# 03_-MPU6050.net
KiCad netlist of a schematic drawn in Altium Designer
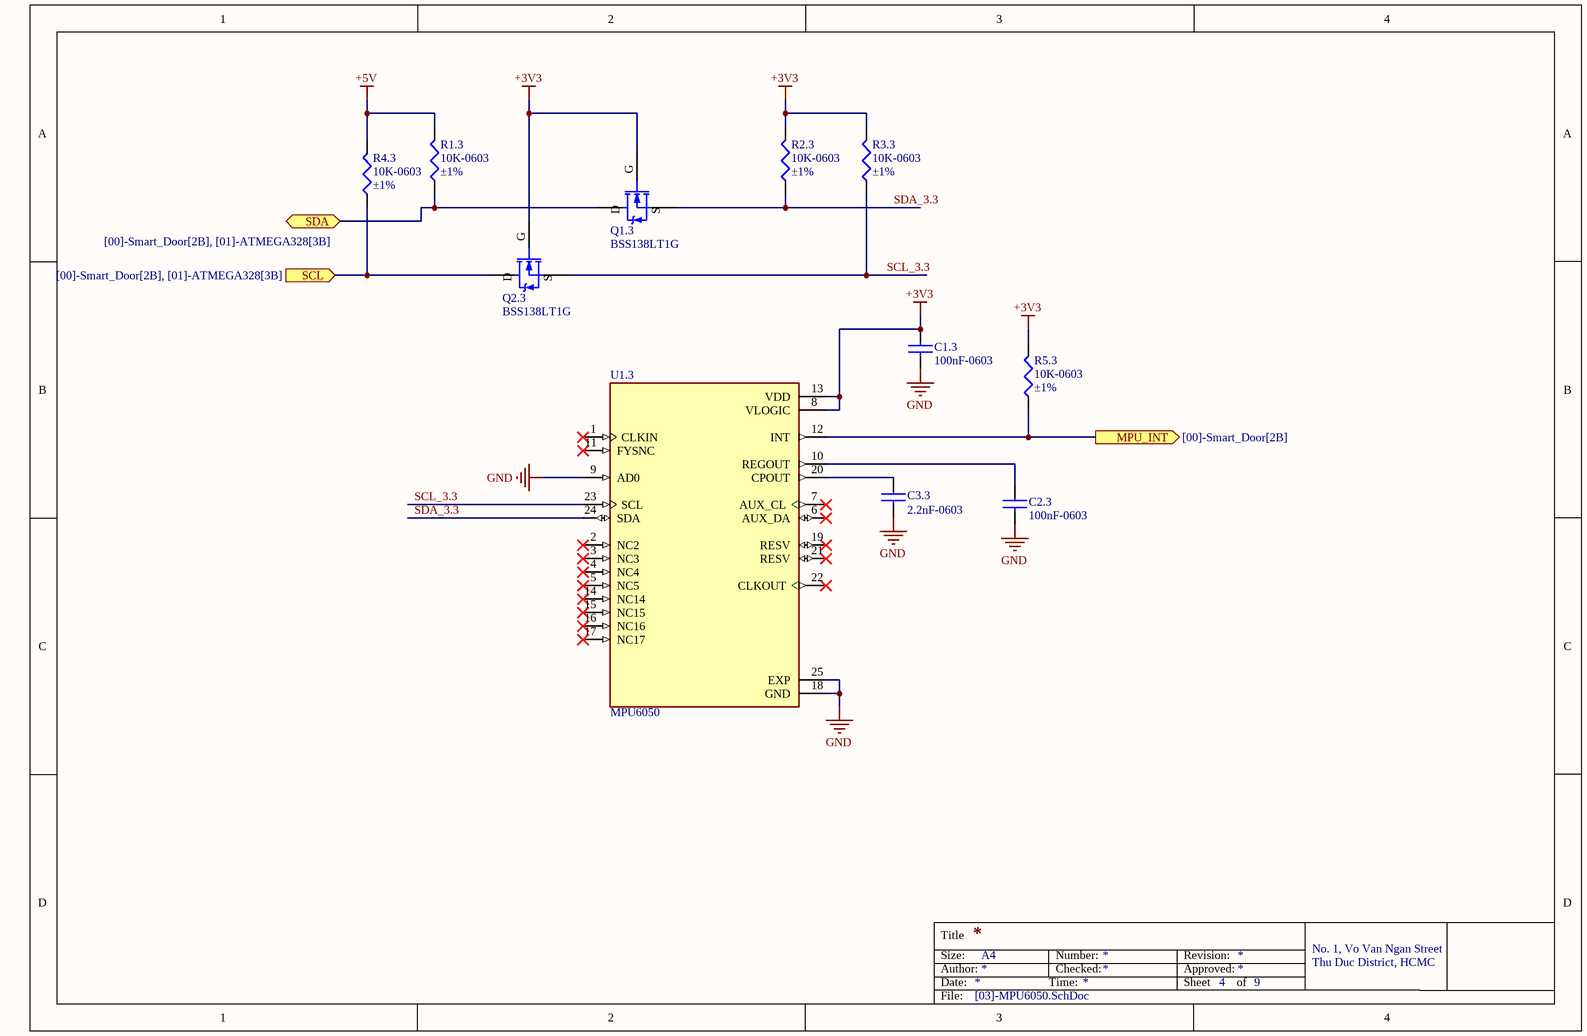
[diagram p0: [03]-MPU6050.SchDoc]

(export (version "E")
  (design (tool "Eeschema 10.0.6"))
  (components
    (comp (ref "C1.3")
      (value "100nF-0603")
      (footprint "CAP0603")
      (description "CAP CER 0.1UF 50V X7R 0603")
      (fields (field (name "TOLERANCE") "±10%"))
      (libsource (lib "Indruino") (part "CC0603KRX7R9BB104"))
    )
    (comp (ref "C2.3")
      (value "100nF-0603")
      (footprint "CAP0603")
      (description "CAP CER 0.1UF 50V X7R 0603")
      (fields (field (name "TOLERANCE") "±10%"))
      (libsource (lib "Indruino") (part "CC0603KRX7R9BB104"))
    )
    (comp (ref "C3.3")
      (value "2.2nF-0603")
      (footprint "CAP0603")
      (description "Multilayer Ceramic Capacitors MLCC - SMD/SMT 2200PF 50V 10% 0603")
      (fields
        (field (name "MANUFACTURER") "Yageo")
        (field (name "MANUFACTURER PART NUMBER") "CC0603KRX7R9BB222")
      )
      (libsource (lib "Indruino") (part "CC0603KRX7R9BB222"))
    )
    (comp (ref "Q1.3")
      (value "BSS138LT1G")
      (footprint "SOT23")
      (description "MOSFET N-CH 50V 200MA SOT-23")
      (fields (field (name "MANUFACTURER") "ON Semiconductor"))
      (libsource (lib "Indruino") (part "BSS138LT1G"))
    )
    (comp (ref "Q2.3")
      (value "BSS138LT1G")
      (footprint "SOT23")
      (description "MOSFET N-CH 50V 200MA SOT-23")
      (fields (field (name "MANUFACTURER") "ON Semiconductor"))
      (libsource (lib "Indruino") (part "BSS138LT1G"))
    )
    (comp (ref "R1.3")
      (value "10K-0603")
      (footprint "RES0603")
      (description "RES SMD 10K OHM 1% 1/10W 0603")
      (fields
        (field (name "MANUFACTURER") "Yageo")
        (field (name "MANUFACTURER PART NUMBER") "RC0603FR-0710KL")
        (field (name "TOLERANCE") "±1%")
      )
      (libsource (lib "Indruino") (part "RC0603FR-0710KL"))
    )
    (comp (ref "R2.3")
      (value "10K-0603")
      (footprint "RES0603")
      (description "RES SMD 10K OHM 1% 1/10W 0603")
      (fields
        (field (name "MANUFACTURER") "Yageo")
        (field (name "MANUFACTURER PART NUMBER") "RC0603FR-0710KL")
        (field (name "TOLERANCE") "±1%")
      )
      (libsource (lib "Indruino") (part "RC0603FR-0710KL"))
    )
    (comp (ref "R3.3")
      (value "10K-0603")
      (footprint "RES0603")
      (description "RES SMD 10K OHM 1% 1/10W 0603")
      (fields
        (field (name "MANUFACTURER") "Yageo")
        (field (name "MANUFACTURER PART NUMBER") "RC0603FR-0710KL")
        (field (name "TOLERANCE") "±1%")
      )
      (libsource (lib "Indruino") (part "RC0603FR-0710KL"))
    )
    (comp (ref "R4.3")
      (value "10K-0603")
      (footprint "RES0603")
      (description "RES SMD 10K OHM 1% 1/10W 0603")
      (fields
        (field (name "MANUFACTURER") "Yageo")
        (field (name "MANUFACTURER PART NUMBER") "RC0603FR-0710KL")
        (field (name "TOLERANCE") "±1%")
      )
      (libsource (lib "Indruino") (part "RC0603FR-0710KL"))
    )
    (comp (ref "R5.3")
      (value "10K-0603")
      (footprint "RES0603")
      (description "RES SMD 10K OHM 1% 1/10W 0603")
      (fields
        (field (name "MANUFACTURER") "Yageo")
        (field (name "MANUFACTURER PART NUMBER") "RC0603FR-0710KL")
        (field (name "TOLERANCE") "±1%")
      )
      (libsource (lib "Indruino") (part "RC0603FR-0710KL"))
    )
    (comp (ref "U1.3")
      (value "MPU6050")
      (footprint "AZ_Lib:IC_MPU6050")
      (description "Accelerometer, Gyroscope, 6 Axis Sensor IÂ²C Output")
      (fields (field (name "MF") "TDK InvenSense"))
      (libsource (lib "AZ_Lib") (part "MPU6050"))
    )
  )
  (nets
    (net (code "1") (name "+3V3") (class "Default")
      (node (ref "C1.3") (pin "1") (pinfunction "1_1") (pintype "passive"))
      (node (ref "Q1.3") (pin "1") (pinfunction "G_1") (pintype "passive"))
      (node (ref "Q2.3") (pin "1") (pinfunction "G_1") (pintype "passive"))
      (node (ref "R2.3") (pin "2") (pinfunction "2_2") (pintype "passive"))
      (node (ref "R3.3") (pin "2") (pinfunction "2_2") (pintype "passive"))
      (node (ref "R5.3") (pin "2") (pinfunction "2_2") (pintype "passive"))
      (node (ref "U1.3") (pin "13") (pinfunction "VDD_13") (pintype "power_in"))
      (node (ref "U1.3") (pin "8") (pinfunction "VLOGIC_8") (pintype "power_in"))
    )
    (net (code "2") (name "+5V") (class "Default")
      (node (ref "R1.3") (pin "2") (pinfunction "2_2") (pintype "passive"))
      (node (ref "R4.3") (pin "2") (pinfunction "2_2") (pintype "passive"))
    )
    (net (code "3") (name "/MPU_INT") (class "Default")
      (node (ref "R5.3") (pin "1") (pinfunction "1_1") (pintype "passive"))
      (node (ref "U1.3") (pin "12") (pinfunction "INT_12") (pintype "output"))
    )
    (net (code "4") (name "/SCL") (class "Default")
      (node (ref "Q2.3") (pin "3") (pinfunction "D_3") (pintype "passive"))
      (node (ref "R4.3") (pin "1") (pinfunction "1_1") (pintype "passive"))
    )
    (net (code "5") (name "/SCL_3.3") (class "Default")
      (node (ref "Q2.3") (pin "2") (pinfunction "S_2") (pintype "passive"))
      (node (ref "R3.3") (pin "1") (pinfunction "1_1") (pintype "passive"))
      (node (ref "U1.3") (pin "23") (pinfunction "SCL_23") (pintype "input"))
    )
    (net (code "6") (name "/SDA") (class "Default")
      (node (ref "Q1.3") (pin "3") (pinfunction "D_3") (pintype "passive"))
      (node (ref "R1.3") (pin "1") (pinfunction "1_1") (pintype "passive"))
    )
    (net (code "7") (name "/SDA_3.3") (class "Default")
      (node (ref "Q1.3") (pin "2") (pinfunction "S_2") (pintype "passive"))
      (node (ref "R2.3") (pin "1") (pinfunction "1_1") (pintype "passive"))
      (node (ref "U1.3") (pin "24") (pinfunction "SDA_24") (pintype "bidirectional"))
    )
    (net (code "8") (name "GND") (class "Default")
      (node (ref "C1.3") (pin "2") (pinfunction "2_2") (pintype "passive"))
      (node (ref "C2.3") (pin "2") (pinfunction "2_2") (pintype "passive"))
      (node (ref "C3.3") (pin "2") (pinfunction "2_2") (pintype "passive"))
      (node (ref "U1.3") (pin "18") (pinfunction "GND_18") (pintype "power_in"))
      (node (ref "U1.3") (pin "25") (pinfunction "EXP_25") (pintype "power_in"))
      (node (ref "U1.3") (pin "9") (pinfunction "AD0_9") (pintype "input"))
    )
    (net (code "9") (name "Net-(U1.3-CPOUT)") (class "Default")
      (node (ref "C3.3") (pin "1") (pinfunction "1_1") (pintype "passive"))
      (node (ref "U1.3") (pin "20") (pinfunction "CPOUT_20") (pintype "output"))
    )
    (net (code "10") (name "Net-(U1.3-REGOUT)") (class "Default")
      (node (ref "C2.3") (pin "1") (pinfunction "1_1") (pintype "passive"))
      (node (ref "U1.3") (pin "10") (pinfunction "REGOUT_10") (pintype "output"))
    )
    (net (code "11") (name "unconnected-(U1.3-AUX_CL-Pad7)") (class "Default")
      (node (ref "U1.3") (pin "7") (pinfunction "AUX_CL_7") (pintype "output+no_connect"))
    )
    (net (code "12") (name "unconnected-(U1.3-AUX_DA-Pad6)") (class "Default")
      (node (ref "U1.3") (pin "6") (pinfunction "AUX_DA_6") (pintype "bidirectional+no_connect"))
    )
    (net (code "13") (name "unconnected-(U1.3-CLKIN-Pad1)") (class "Default")
      (node (ref "U1.3") (pin "1") (pinfunction "CLKIN_1") (pintype "input+no_connect"))
    )
    (net (code "14") (name "unconnected-(U1.3-CLKOUT-Pad22)") (class "Default")
      (node (ref "U1.3") (pin "22") (pinfunction "CLKOUT_22") (pintype "output+no_connect"))
    )
    (net (code "15") (name "unconnected-(U1.3-FYSNC-Pad11)") (class "Default")
      (node (ref "U1.3") (pin "11") (pinfunction "FYSNC_11") (pintype "input+no_connect"))
    )
    (net (code "16") (name "unconnected-(U1.3-NC2-Pad2)") (class "Default")
      (node (ref "U1.3") (pin "2") (pinfunction "NC2_2") (pintype "input+no_connect"))
    )
    (net (code "17") (name "unconnected-(U1.3-NC3-Pad3)") (class "Default")
      (node (ref "U1.3") (pin "3") (pinfunction "NC3_3") (pintype "input+no_connect"))
    )
    (net (code "18") (name "unconnected-(U1.3-NC4-Pad4)") (class "Default")
      (node (ref "U1.3") (pin "4") (pinfunction "NC4_4") (pintype "input+no_connect"))
    )
    (net (code "19") (name "unconnected-(U1.3-NC5-Pad5)") (class "Default")
      (node (ref "U1.3") (pin "5") (pinfunction "NC5_5") (pintype "input+no_connect"))
    )
    (net (code "20") (name "unconnected-(U1.3-NC14-Pad14)") (class "Default")
      (node (ref "U1.3") (pin "14") (pinfunction "NC14_14") (pintype "input+no_connect"))
    )
    (net (code "21") (name "unconnected-(U1.3-NC15-Pad15)") (class "Default")
      (node (ref "U1.3") (pin "15") (pinfunction "NC15_15") (pintype "input+no_connect"))
    )
    (net (code "22") (name "unconnected-(U1.3-NC16-Pad16)") (class "Default")
      (node (ref "U1.3") (pin "16") (pinfunction "NC16_16") (pintype "input+no_connect"))
    )
    (net (code "23") (name "unconnected-(U1.3-NC17-Pad17)") (class "Default")
      (node (ref "U1.3") (pin "17") (pinfunction "NC17_17") (pintype "input+no_connect"))
    )
    (net (code "24") (name "unconnected-(U1.3-RESV-Pad19)") (class "Default")
      (node (ref "U1.3") (pin "19") (pinfunction "RESV_19") (pintype "bidirectional+no_connect"))
    )
    (net (code "25") (name "unconnected-(U1.3-RESV-Pad21)") (class "Default")
      (node (ref "U1.3") (pin "21") (pinfunction "RESV_21") (pintype "bidirectional+no_connect"))
    )
  )
)
